# PowerIOShield.net
KiCad netlist of a schematic drawn in EAGLE
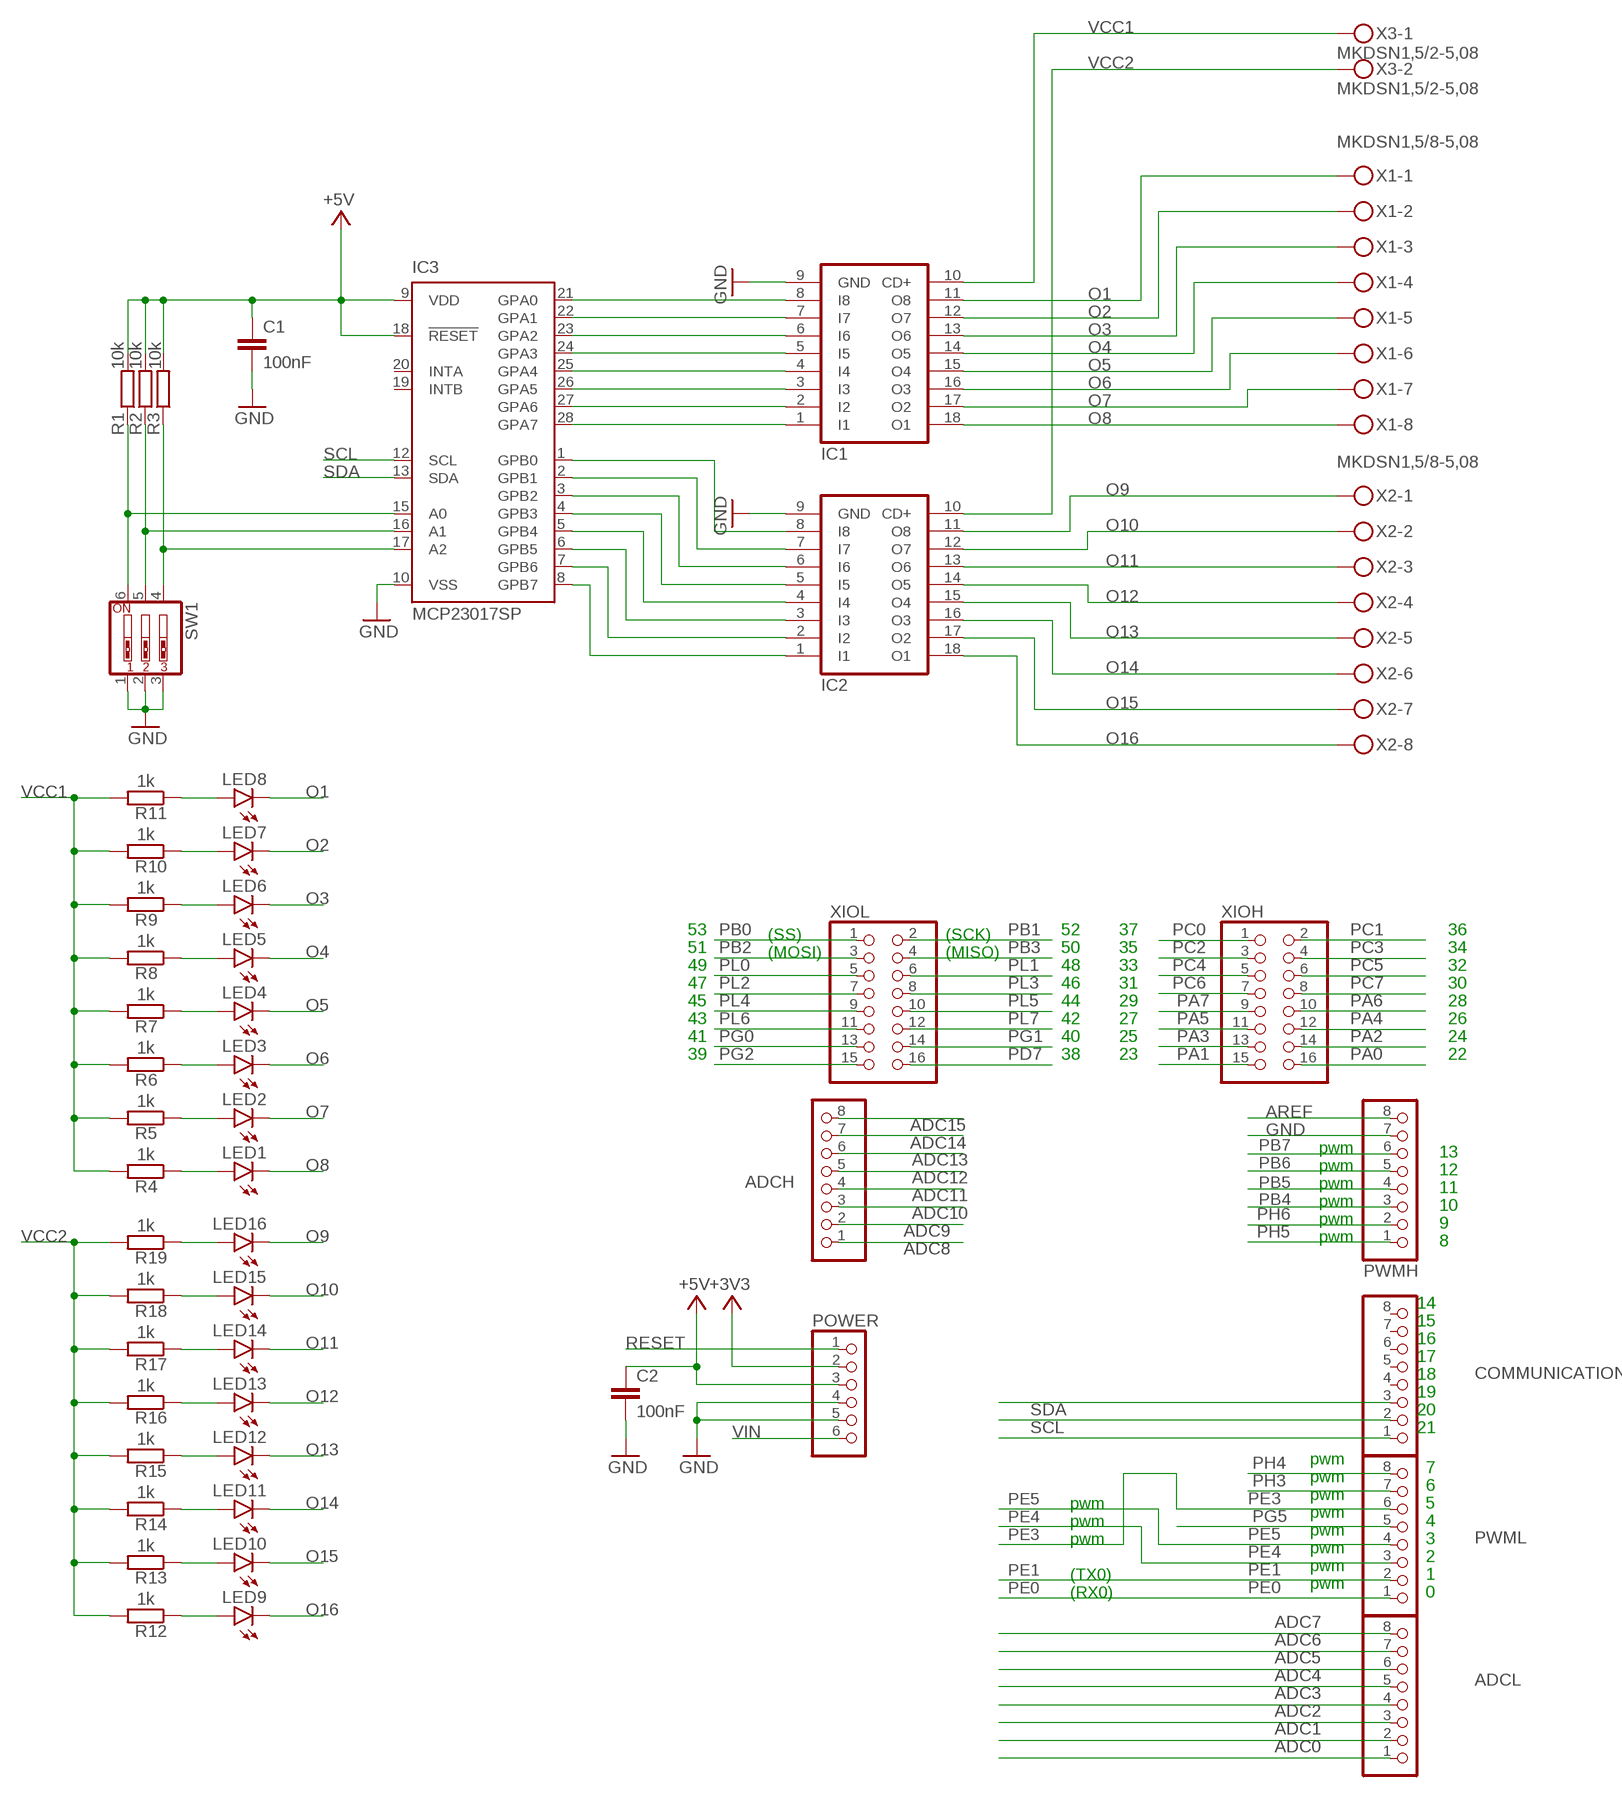
[diagram p0: schematic, sheet 1]

(export (version "E")
  (design (tool "Eeschema 10.0.6"))
  (components
    (comp (ref "ADCH")
      (value "PINHD-1X8")
      (footprint "eagle-import:1X08")
      (libsource (lib "eagle-import") (part "PINHD-1X8"))
    )
    (comp (ref "ADCL")
      (value "PINHD-1X8")
      (footprint "eagle-import:1X08")
      (libsource (lib "eagle-import") (part "PINHD-1X8"))
    )
    (comp (ref "C1")
      (value "100nF")
      (footprint "eagle-import:C025-024X044")
      (libsource (lib "eagle-import") (part "C-EU025-024X044"))
    )
    (comp (ref "C2")
      (value "100nF")
      (footprint "eagle-import:C025-024X044")
      (libsource (lib "eagle-import") (part "C-EU025-024X044"))
    )
    (comp (ref "COMMUNICATION")
      (value "PINHD-1X8")
      (footprint "eagle-import:1X08")
      (libsource (lib "eagle-import") (part "PINHD-1X8"))
    )
    (comp (ref "IC1")
      (value "ULN2803A")
      (footprint "eagle-import:DIL18")
      (libsource (lib "eagle-import") (part "ULN2803A"))
    )
    (comp (ref "IC2")
      (value "ULN2803A")
      (footprint "eagle-import:DIL18")
      (libsource (lib "eagle-import") (part "ULN2803A"))
    )
    (comp (ref "IC3")
      (value "MCP23017SP")
      (footprint "eagle-import:DIL28-3")
      (fields (field (name "MF") "MICROCHIP") (field (name "MPN") "MCP23017-E/SP"))
      (libsource (lib "eagle-import") (part "MCP23017SP"))
    )
    (comp (ref "LED1")
      (value "LED3MM")
      (footprint "eagle-import:LED3MM")
      (libsource (lib "eagle-import") (part "LED3MM"))
    )
    (comp (ref "LED2")
      (value "LED3MM")
      (footprint "eagle-import:LED3MM")
      (libsource (lib "eagle-import") (part "LED3MM"))
    )
    (comp (ref "LED3")
      (value "LED3MM")
      (footprint "eagle-import:LED3MM")
      (libsource (lib "eagle-import") (part "LED3MM"))
    )
    (comp (ref "LED4")
      (value "LED3MM")
      (footprint "eagle-import:LED3MM")
      (libsource (lib "eagle-import") (part "LED3MM"))
    )
    (comp (ref "LED5")
      (value "LED3MM")
      (footprint "eagle-import:LED3MM")
      (libsource (lib "eagle-import") (part "LED3MM"))
    )
    (comp (ref "LED6")
      (value "LED3MM")
      (footprint "eagle-import:LED3MM")
      (libsource (lib "eagle-import") (part "LED3MM"))
    )
    (comp (ref "LED7")
      (value "LED3MM")
      (footprint "eagle-import:LED3MM")
      (libsource (lib "eagle-import") (part "LED3MM"))
    )
    (comp (ref "LED8")
      (value "LED3MM")
      (footprint "eagle-import:LED3MM")
      (libsource (lib "eagle-import") (part "LED3MM"))
    )
    (comp (ref "LED9")
      (value "LED3MM")
      (footprint "eagle-import:LED3MM")
      (libsource (lib "eagle-import") (part "LED3MM"))
    )
    (comp (ref "LED10")
      (value "LED3MM")
      (footprint "eagle-import:LED3MM")
      (libsource (lib "eagle-import") (part "LED3MM"))
    )
    (comp (ref "LED11")
      (value "LED3MM")
      (footprint "eagle-import:LED3MM")
      (libsource (lib "eagle-import") (part "LED3MM"))
    )
    (comp (ref "LED12")
      (value "LED3MM")
      (footprint "eagle-import:LED3MM")
      (libsource (lib "eagle-import") (part "LED3MM"))
    )
    (comp (ref "LED13")
      (value "LED3MM")
      (footprint "eagle-import:LED3MM")
      (libsource (lib "eagle-import") (part "LED3MM"))
    )
    (comp (ref "LED14")
      (value "LED3MM")
      (footprint "eagle-import:LED3MM")
      (libsource (lib "eagle-import") (part "LED3MM"))
    )
    (comp (ref "LED15")
      (value "LED3MM")
      (footprint "eagle-import:LED3MM")
      (libsource (lib "eagle-import") (part "LED3MM"))
    )
    (comp (ref "LED16")
      (value "LED3MM")
      (footprint "eagle-import:LED3MM")
      (libsource (lib "eagle-import") (part "LED3MM"))
    )
    (comp (ref "POWER")
      (value "PINHD-1X6")
      (footprint "eagle-import:1X06")
      (libsource (lib "eagle-import") (part "PINHD-1X6"))
    )
    (comp (ref "PWMH")
      (value "PINHD-1X8")
      (footprint "eagle-import:1X08")
      (libsource (lib "eagle-import") (part "PINHD-1X8"))
    )
    (comp (ref "PWML")
      (value "PINHD-1X8")
      (footprint "eagle-import:1X08")
      (libsource (lib "eagle-import") (part "PINHD-1X8"))
    )
    (comp (ref "R1")
      (value "10k")
      (footprint "eagle-import:0204_7")
      (libsource (lib "eagle-import") (part "R-EU_0204/7"))
    )
    (comp (ref "R2")
      (value "10k")
      (footprint "eagle-import:0204_7")
      (libsource (lib "eagle-import") (part "R-EU_0204/7"))
    )
    (comp (ref "R3")
      (value "10k")
      (footprint "eagle-import:0204_7")
      (libsource (lib "eagle-import") (part "R-EU_0204/7"))
    )
    (comp (ref "R4")
      (value "1k")
      (footprint "eagle-import:0204_7")
      (libsource (lib "eagle-import") (part "R-EU_0204/7"))
    )
    (comp (ref "R5")
      (value "1k")
      (footprint "eagle-import:0204_7")
      (libsource (lib "eagle-import") (part "R-EU_0204/7"))
    )
    (comp (ref "R6")
      (value "1k")
      (footprint "eagle-import:0204_7")
      (libsource (lib "eagle-import") (part "R-EU_0204/7"))
    )
    (comp (ref "R7")
      (value "1k")
      (footprint "eagle-import:0204_7")
      (libsource (lib "eagle-import") (part "R-EU_0204/7"))
    )
    (comp (ref "R8")
      (value "1k")
      (footprint "eagle-import:0204_7")
      (libsource (lib "eagle-import") (part "R-EU_0204/7"))
    )
    (comp (ref "R9")
      (value "1k")
      (footprint "eagle-import:0204_7")
      (libsource (lib "eagle-import") (part "R-EU_0204/7"))
    )
    (comp (ref "R10")
      (value "1k")
      (footprint "eagle-import:0204_7")
      (libsource (lib "eagle-import") (part "R-EU_0204/7"))
    )
    (comp (ref "R11")
      (value "1k")
      (footprint "eagle-import:0204_7")
      (libsource (lib "eagle-import") (part "R-EU_0204/7"))
    )
    (comp (ref "R12")
      (value "1k")
      (footprint "eagle-import:0204_7")
      (libsource (lib "eagle-import") (part "R-EU_0204/7"))
    )
    (comp (ref "R13")
      (value "1k")
      (footprint "eagle-import:0204_7")
      (libsource (lib "eagle-import") (part "R-EU_0204/7"))
    )
    (comp (ref "R14")
      (value "1k")
      (footprint "eagle-import:0204_7")
      (libsource (lib "eagle-import") (part "R-EU_0204/7"))
    )
    (comp (ref "R15")
      (value "1k")
      (footprint "eagle-import:0204_7")
      (libsource (lib "eagle-import") (part "R-EU_0204/7"))
    )
    (comp (ref "R16")
      (value "1k")
      (footprint "eagle-import:0204_7")
      (libsource (lib "eagle-import") (part "R-EU_0204/7"))
    )
    (comp (ref "R17")
      (value "1k")
      (footprint "eagle-import:0204_7")
      (libsource (lib "eagle-import") (part "R-EU_0204/7"))
    )
    (comp (ref "R18")
      (value "1k")
      (footprint "eagle-import:0204_7")
      (libsource (lib "eagle-import") (part "R-EU_0204/7"))
    )
    (comp (ref "R19")
      (value "1k")
      (footprint "eagle-import:0204_7")
      (libsource (lib "eagle-import") (part "R-EU_0204/7"))
    )
    (comp (ref "SW1")
      (value "SW_DIP-3")
      (footprint "eagle-import:EDG-03")
      (libsource (lib "eagle-import") (part "SW_DIP-3"))
    )
    (comp (ref "X1")
      (value "MKDSN1,5/8-5,08")
      (footprint "eagle-import:MKDSN1,5_8-5,08")
      (libsource (lib "eagle-import") (part "MKDSN1,5/8-5,08"))
    )
    (comp (ref "X2")
      (value "MKDSN1,5/8-5,08")
      (footprint "eagle-import:MKDSN1,5_8-5,08")
      (libsource (lib "eagle-import") (part "MKDSN1,5/8-5,08"))
    )
    (comp (ref "X3")
      (value "MKDSN1,5/2-5,08")
      (footprint "eagle-import:MKDSN1,5_2-5,08")
      (libsource (lib "eagle-import") (part "MKDSN1,5/2-5,08"))
    )
    (comp (ref "XIOH")
      (value "PINHD-2X8")
      (footprint "eagle-import:2X08")
      (libsource (lib "eagle-import") (part "PINHD-2X8"))
    )
    (comp (ref "XIOL")
      (value "PINHD-2X8")
      (footprint "eagle-import:2X08")
      (libsource (lib "eagle-import") (part "PINHD-2X8"))
    )
  )
  (nets
    (net (code "1") (name "+3V3") (class "Default")
      (node (ref "POWER") (pin "2") (pinfunction "2_2") (pintype "passive"))
    )
    (net (code "2") (name "+5V") (class "Default")
      (node (ref "C1") (pin "1") (pinfunction "1_1") (pintype "passive"))
      (node (ref "C2") (pin "1") (pinfunction "1_1") (pintype "passive"))
      (node (ref "IC3") (pin "18") (pinfunction "~{RESET}_18") (pintype "input"))
      (node (ref "IC3") (pin "9") (pinfunction "VDD_9") (pintype "power_in"))
      (node (ref "POWER") (pin "3") (pinfunction "3_3") (pintype "passive"))
      (node (ref "R1") (pin "2") (pinfunction "2_2") (pintype "passive"))
      (node (ref "R2") (pin "2") (pinfunction "2_2") (pintype "passive"))
      (node (ref "R3") (pin "2") (pinfunction "2_2") (pintype "passive"))
    )
    (net (code "3") (name "/ADC0") (class "Default")
      (node (ref "ADCL") (pin "1") (pinfunction "1_1") (pintype "passive"))
    )
    (net (code "4") (name "/ADC1") (class "Default")
      (node (ref "ADCL") (pin "2") (pinfunction "2_2") (pintype "passive"))
    )
    (net (code "5") (name "/ADC2") (class "Default")
      (node (ref "ADCL") (pin "3") (pinfunction "3_3") (pintype "passive"))
    )
    (net (code "6") (name "/ADC3") (class "Default")
      (node (ref "ADCL") (pin "4") (pinfunction "4_4") (pintype "passive"))
    )
    (net (code "7") (name "/ADC4") (class "Default")
      (node (ref "ADCL") (pin "5") (pinfunction "5_5") (pintype "passive"))
    )
    (net (code "8") (name "/ADC5") (class "Default")
      (node (ref "ADCL") (pin "6") (pinfunction "6_6") (pintype "passive"))
    )
    (net (code "9") (name "/ADC6") (class "Default")
      (node (ref "ADCL") (pin "7") (pinfunction "7_7") (pintype "passive"))
    )
    (net (code "10") (name "/ADC7") (class "Default")
      (node (ref "ADCL") (pin "8") (pinfunction "8_8") (pintype "passive"))
    )
    (net (code "11") (name "/ADC8") (class "Default")
      (node (ref "ADCH") (pin "1") (pinfunction "1_1") (pintype "passive"))
    )
    (net (code "12") (name "/ADC9") (class "Default")
      (node (ref "ADCH") (pin "2") (pinfunction "2_2") (pintype "passive"))
    )
    (net (code "13") (name "/ADC10") (class "Default")
      (node (ref "ADCH") (pin "3") (pinfunction "3_3") (pintype "passive"))
    )
    (net (code "14") (name "/ADC11") (class "Default")
      (node (ref "ADCH") (pin "4") (pinfunction "4_4") (pintype "passive"))
    )
    (net (code "15") (name "/ADC12") (class "Default")
      (node (ref "ADCH") (pin "5") (pinfunction "5_5") (pintype "passive"))
    )
    (net (code "16") (name "/ADC13") (class "Default")
      (node (ref "ADCH") (pin "6") (pinfunction "6_6") (pintype "passive"))
    )
    (net (code "17") (name "/ADC14") (class "Default")
      (node (ref "ADCH") (pin "7") (pinfunction "7_7") (pintype "passive"))
    )
    (net (code "18") (name "/ADC15") (class "Default")
      (node (ref "ADCH") (pin "8") (pinfunction "8_8") (pintype "passive"))
    )
    (net (code "19") (name "/AREF") (class "Default")
      (node (ref "PWMH") (pin "8") (pinfunction "8_8") (pintype "passive"))
    )
    (net (code "20") (name "/O1") (class "Default")
      (node (ref "IC1") (pin "11") (pinfunction "O8_11") (pintype "open_collector"))
      (node (ref "LED8") (pin "K") (pinfunction "C_K") (pintype "passive"))
      (node (ref "X1") (pin "1") (pinfunction "KL_1") (pintype "passive"))
    )
    (net (code "21") (name "/O2") (class "Default")
      (node (ref "IC1") (pin "12") (pinfunction "O7_12") (pintype "open_collector"))
      (node (ref "LED7") (pin "K") (pinfunction "C_K") (pintype "passive"))
      (node (ref "X1") (pin "2") (pinfunction "KL_2") (pintype "passive"))
    )
    (net (code "22") (name "/O3") (class "Default")
      (node (ref "IC1") (pin "13") (pinfunction "O6_13") (pintype "open_collector"))
      (node (ref "LED6") (pin "K") (pinfunction "C_K") (pintype "passive"))
      (node (ref "X1") (pin "3") (pinfunction "KL_3") (pintype "passive"))
    )
    (net (code "23") (name "/O4") (class "Default")
      (node (ref "IC1") (pin "14") (pinfunction "O5_14") (pintype "open_collector"))
      (node (ref "LED5") (pin "K") (pinfunction "C_K") (pintype "passive"))
      (node (ref "X1") (pin "4") (pinfunction "KL_4") (pintype "passive"))
    )
    (net (code "24") (name "/O5") (class "Default")
      (node (ref "IC1") (pin "15") (pinfunction "O4_15") (pintype "open_collector"))
      (node (ref "LED4") (pin "K") (pinfunction "C_K") (pintype "passive"))
      (node (ref "X1") (pin "5") (pinfunction "KL_5") (pintype "passive"))
    )
    (net (code "25") (name "/O6") (class "Default")
      (node (ref "IC1") (pin "16") (pinfunction "O3_16") (pintype "open_collector"))
      (node (ref "LED3") (pin "K") (pinfunction "C_K") (pintype "passive"))
      (node (ref "X1") (pin "6") (pinfunction "KL_6") (pintype "passive"))
    )
    (net (code "26") (name "/O7") (class "Default")
      (node (ref "IC1") (pin "17") (pinfunction "O2_17") (pintype "open_collector"))
      (node (ref "LED2") (pin "K") (pinfunction "C_K") (pintype "passive"))
      (node (ref "X1") (pin "7") (pinfunction "KL_7") (pintype "passive"))
    )
    (net (code "27") (name "/O8") (class "Default")
      (node (ref "IC1") (pin "18") (pinfunction "O1_18") (pintype "open_collector"))
      (node (ref "LED1") (pin "K") (pinfunction "C_K") (pintype "passive"))
      (node (ref "X1") (pin "8") (pinfunction "KL_8") (pintype "passive"))
    )
    (net (code "28") (name "/O9") (class "Default")
      (node (ref "IC2") (pin "11") (pinfunction "O8_11") (pintype "open_collector"))
      (node (ref "LED16") (pin "K") (pinfunction "C_K") (pintype "passive"))
      (node (ref "X2") (pin "1") (pinfunction "KL_1") (pintype "passive"))
    )
    (net (code "29") (name "/O10") (class "Default")
      (node (ref "IC2") (pin "12") (pinfunction "O7_12") (pintype "open_collector"))
      (node (ref "LED15") (pin "K") (pinfunction "C_K") (pintype "passive"))
      (node (ref "X2") (pin "2") (pinfunction "KL_2") (pintype "passive"))
    )
    (net (code "30") (name "/O11") (class "Default")
      (node (ref "IC2") (pin "13") (pinfunction "O6_13") (pintype "open_collector"))
      (node (ref "LED14") (pin "K") (pinfunction "C_K") (pintype "passive"))
      (node (ref "X2") (pin "3") (pinfunction "KL_3") (pintype "passive"))
    )
    (net (code "31") (name "/O12") (class "Default")
      (node (ref "IC2") (pin "14") (pinfunction "O5_14") (pintype "open_collector"))
      (node (ref "LED13") (pin "K") (pinfunction "C_K") (pintype "passive"))
      (node (ref "X2") (pin "4") (pinfunction "KL_4") (pintype "passive"))
    )
    (net (code "32") (name "/O13") (class "Default")
      (node (ref "IC2") (pin "15") (pinfunction "O4_15") (pintype "open_collector"))
      (node (ref "LED12") (pin "K") (pinfunction "C_K") (pintype "passive"))
      (node (ref "X2") (pin "5") (pinfunction "KL_5") (pintype "passive"))
    )
    (net (code "33") (name "/O14") (class "Default")
      (node (ref "IC2") (pin "16") (pinfunction "O3_16") (pintype "open_collector"))
      (node (ref "LED11") (pin "K") (pinfunction "C_K") (pintype "passive"))
      (node (ref "X2") (pin "6") (pinfunction "KL_6") (pintype "passive"))
    )
    (net (code "34") (name "/O15") (class "Default")
      (node (ref "IC2") (pin "17") (pinfunction "O2_17") (pintype "open_collector"))
      (node (ref "LED10") (pin "K") (pinfunction "C_K") (pintype "passive"))
      (node (ref "X2") (pin "7") (pinfunction "KL_7") (pintype "passive"))
    )
    (net (code "35") (name "/O16") (class "Default")
      (node (ref "IC2") (pin "18") (pinfunction "O1_18") (pintype "open_collector"))
      (node (ref "LED9") (pin "K") (pinfunction "C_K") (pintype "passive"))
      (node (ref "X2") (pin "8") (pinfunction "KL_8") (pintype "passive"))
    )
    (net (code "36") (name "/PA0") (class "Default")
      (node (ref "XIOH") (pin "16") (pinfunction "16_16") (pintype "passive"))
    )
    (net (code "37") (name "/PA1") (class "Default")
      (node (ref "XIOH") (pin "15") (pinfunction "15_15") (pintype "passive"))
    )
    (net (code "38") (name "/PA2") (class "Default")
      (node (ref "XIOH") (pin "14") (pinfunction "14_14") (pintype "passive"))
    )
    (net (code "39") (name "/PA3") (class "Default")
      (node (ref "XIOH") (pin "13") (pinfunction "13_13") (pintype "passive"))
    )
    (net (code "40") (name "/PA4") (class "Default")
      (node (ref "XIOH") (pin "12") (pinfunction "12_12") (pintype "passive"))
    )
    (net (code "41") (name "/PA5") (class "Default")
      (node (ref "XIOH") (pin "11") (pinfunction "11_11") (pintype "passive"))
    )
    (net (code "42") (name "/PA6") (class "Default")
      (node (ref "XIOH") (pin "10") (pinfunction "10_10") (pintype "passive"))
    )
    (net (code "43") (name "/PA7") (class "Default")
      (node (ref "XIOH") (pin "9") (pinfunction "9_9") (pintype "passive"))
    )
    (net (code "44") (name "/PB0") (class "Default")
      (node (ref "XIOL") (pin "1") (pinfunction "1_1") (pintype "passive"))
    )
    (net (code "45") (name "/PB1") (class "Default")
      (node (ref "XIOL") (pin "2") (pinfunction "2_2") (pintype "passive"))
    )
    (net (code "46") (name "/PB2") (class "Default")
      (node (ref "XIOL") (pin "3") (pinfunction "3_3") (pintype "passive"))
    )
    (net (code "47") (name "/PB3") (class "Default")
      (node (ref "XIOL") (pin "4") (pinfunction "4_4") (pintype "passive"))
    )
    (net (code "48") (name "/PB4") (class "Default")
      (node (ref "PWMH") (pin "3") (pinfunction "3_3") (pintype "passive"))
    )
    (net (code "49") (name "/PB5") (class "Default")
      (node (ref "PWMH") (pin "4") (pinfunction "4_4") (pintype "passive"))
    )
    (net (code "50") (name "/PB6") (class "Default")
      (node (ref "PWMH") (pin "5") (pinfunction "5_5") (pintype "passive"))
    )
    (net (code "51") (name "/PB7") (class "Default")
      (node (ref "PWMH") (pin "6") (pinfunction "6_6") (pintype "passive"))
    )
    (net (code "52") (name "/PC0") (class "Default")
      (node (ref "XIOH") (pin "1") (pinfunction "1_1") (pintype "passive"))
    )
    (net (code "53") (name "/PC1") (class "Default")
      (node (ref "XIOH") (pin "2") (pinfunction "2_2") (pintype "passive"))
    )
    (net (code "54") (name "/PC2") (class "Default")
      (node (ref "XIOH") (pin "3") (pinfunction "3_3") (pintype "passive"))
    )
    (net (code "55") (name "/PC3") (class "Default")
      (node (ref "XIOH") (pin "4") (pinfunction "4_4") (pintype "passive"))
    )
    (net (code "56") (name "/PC4") (class "Default")
      (node (ref "XIOH") (pin "5") (pinfunction "5_5") (pintype "passive"))
    )
    (net (code "57") (name "/PC5") (class "Default")
      (node (ref "XIOH") (pin "6") (pinfunction "6_6") (pintype "passive"))
    )
    (net (code "58") (name "/PC6") (class "Default")
      (node (ref "XIOH") (pin "7") (pinfunction "7_7") (pintype "passive"))
    )
    (net (code "59") (name "/PC7") (class "Default")
      (node (ref "XIOH") (pin "8") (pinfunction "8_8") (pintype "passive"))
    )
    (net (code "60") (name "/PD7") (class "Default")
      (node (ref "XIOL") (pin "16") (pinfunction "16_16") (pintype "passive"))
    )
    (net (code "61") (name "/PE0") (class "Default")
      (node (ref "PWML") (pin "1") (pinfunction "1_1") (pintype "passive"))
    )
    (net (code "62") (name "/PE1") (class "Default")
      (node (ref "PWML") (pin "2") (pinfunction "2_2") (pintype "passive"))
    )
    (net (code "63") (name "/PE3") (class "Default")
      (node (ref "PWML") (pin "6") (pinfunction "6_6") (pintype "passive"))
    )
    (net (code "64") (name "/PE4") (class "Default")
      (node (ref "PWML") (pin "3") (pinfunction "3_3") (pintype "passive"))
    )
    (net (code "65") (name "/PE5") (class "Default")
      (node (ref "PWML") (pin "4") (pinfunction "4_4") (pintype "passive"))
    )
    (net (code "66") (name "/PG0") (class "Default")
      (node (ref "XIOL") (pin "13") (pinfunction "13_13") (pintype "passive"))
    )
    (net (code "67") (name "/PG1") (class "Default")
      (node (ref "XIOL") (pin "14") (pinfunction "14_14") (pintype "passive"))
    )
    (net (code "68") (name "/PG2") (class "Default")
      (node (ref "XIOL") (pin "15") (pinfunction "15_15") (pintype "passive"))
    )
    (net (code "69") (name "/PG5") (class "Default")
      (node (ref "PWML") (pin "5") (pinfunction "5_5") (pintype "passive"))
    )
    (net (code "70") (name "/PH3") (class "Default")
      (node (ref "PWML") (pin "7") (pinfunction "7_7") (pintype "passive"))
    )
    (net (code "71") (name "/PH4") (class "Default")
      (node (ref "PWML") (pin "8") (pinfunction "8_8") (pintype "passive"))
    )
    (net (code "72") (name "/PH5") (class "Default")
      (node (ref "PWMH") (pin "1") (pinfunction "1_1") (pintype "passive"))
    )
    (net (code "73") (name "/PH6") (class "Default")
      (node (ref "PWMH") (pin "2") (pinfunction "2_2") (pintype "passive"))
    )
    (net (code "74") (name "/PL0") (class "Default")
      (node (ref "XIOL") (pin "5") (pinfunction "5_5") (pintype "passive"))
    )
    (net (code "75") (name "/PL1") (class "Default")
      (node (ref "XIOL") (pin "6") (pinfunction "6_6") (pintype "passive"))
    )
    (net (code "76") (name "/PL2") (class "Default")
      (node (ref "XIOL") (pin "7") (pinfunction "7_7") (pintype "passive"))
    )
    (net (code "77") (name "/PL3") (class "Default")
      (node (ref "XIOL") (pin "8") (pinfunction "8_8") (pintype "passive"))
    )
    (net (code "78") (name "/PL4") (class "Default")
      (node (ref "XIOL") (pin "9") (pinfunction "9_9") (pintype "passive"))
    )
    (net (code "79") (name "/PL5") (class "Default")
      (node (ref "XIOL") (pin "10") (pinfunction "10_10") (pintype "passive"))
    )
    (net (code "80") (name "/PL6") (class "Default")
      (node (ref "XIOL") (pin "11") (pinfunction "11_11") (pintype "passive"))
    )
    (net (code "81") (name "/PL7") (class "Default")
      (node (ref "XIOL") (pin "12") (pinfunction "12_12") (pintype "passive"))
    )
    (net (code "82") (name "/RESET") (class "Default")
      (node (ref "POWER") (pin "1") (pinfunction "1_1") (pintype "passive"))
    )
    (net (code "83") (name "/SCL") (class "Default")
      (node (ref "COMMUNICATION") (pin "1") (pinfunction "1_1") (pintype "passive"))
      (node (ref "IC3") (pin "12") (pinfunction "SCL_12") (pintype "input"))
    )
    (net (code "84") (name "/SDA") (class "Default")
      (node (ref "COMMUNICATION") (pin "2") (pinfunction "2_2") (pintype "passive"))
      (node (ref "IC3") (pin "13") (pinfunction "SDA_13") (pintype "bidirectional"))
    )
    (net (code "85") (name "/VCC1") (class "Default")
      (node (ref "IC1") (pin "10") (pinfunction "CD+_10") (pintype "passive"))
      (node (ref "R10") (pin "2") (pinfunction "2_2") (pintype "passive"))
      (node (ref "R11") (pin "2") (pinfunction "2_2") (pintype "passive"))
      (node (ref "R4") (pin "2") (pinfunction "2_2") (pintype "passive"))
      (node (ref "R5") (pin "2") (pinfunction "2_2") (pintype "passive"))
      (node (ref "R6") (pin "2") (pinfunction "2_2") (pintype "passive"))
      (node (ref "R7") (pin "2") (pinfunction "2_2") (pintype "passive"))
      (node (ref "R8") (pin "2") (pinfunction "2_2") (pintype "passive"))
      (node (ref "R9") (pin "2") (pinfunction "2_2") (pintype "passive"))
      (node (ref "X3") (pin "1") (pinfunction "KL_1") (pintype "passive"))
    )
    (net (code "86") (name "/VCC2") (class "Default")
      (node (ref "IC2") (pin "10") (pinfunction "CD+_10") (pintype "passive"))
      (node (ref "R12") (pin "2") (pinfunction "2_2") (pintype "passive"))
      (node (ref "R13") (pin "2") (pinfunction "2_2") (pintype "passive"))
      (node (ref "R14") (pin "2") (pinfunction "2_2") (pintype "passive"))
      (node (ref "R15") (pin "2") (pinfunction "2_2") (pintype "passive"))
      (node (ref "R16") (pin "2") (pinfunction "2_2") (pintype "passive"))
      (node (ref "R17") (pin "2") (pinfunction "2_2") (pintype "passive"))
      (node (ref "R18") (pin "2") (pinfunction "2_2") (pintype "passive"))
      (node (ref "R19") (pin "2") (pinfunction "2_2") (pintype "passive"))
      (node (ref "X3") (pin "2") (pinfunction "KL_2") (pintype "passive"))
    )
    (net (code "87") (name "/VIN") (class "Default")
      (node (ref "POWER") (pin "6") (pinfunction "6_6") (pintype "passive"))
    )
    (net (code "88") (name "GND") (class "Default")
      (node (ref "C1") (pin "2") (pinfunction "2_2") (pintype "passive"))
      (node (ref "C2") (pin "2") (pinfunction "2_2") (pintype "passive"))
      (node (ref "IC1") (pin "9") (pinfunction "GND_9") (pintype "power_in"))
      (node (ref "IC2") (pin "9") (pinfunction "GND_9") (pintype "power_in"))
      (node (ref "IC3") (pin "10") (pinfunction "VSS_10") (pintype "power_in"))
      (node (ref "POWER") (pin "4") (pinfunction "4_4") (pintype "passive"))
      (node (ref "POWER") (pin "5") (pinfunction "5_5") (pintype "passive"))
      (node (ref "PWMH") (pin "7") (pinfunction "7_7") (pintype "passive"))
      (node (ref "SW1") (pin "1") (pinfunction "1_1") (pintype "passive"))
      (node (ref "SW1") (pin "2") (pinfunction "2_2") (pintype "passive"))
      (node (ref "SW1") (pin "3") (pinfunction "3_3") (pintype "passive"))
    )
    (net (code "89") (name "Net-(IC1-I1)") (class "Default")
      (node (ref "IC1") (pin "1") (pinfunction "I1_1") (pintype "input"))
      (node (ref "IC3") (pin "28") (pinfunction "GPA7_28") (pintype "bidirectional"))
    )
    (net (code "90") (name "Net-(IC1-I2)") (class "Default")
      (node (ref "IC1") (pin "2") (pinfunction "I2_2") (pintype "input"))
      (node (ref "IC3") (pin "27") (pinfunction "GPA6_27") (pintype "bidirectional"))
    )
    (net (code "91") (name "Net-(IC1-I3)") (class "Default")
      (node (ref "IC1") (pin "3") (pinfunction "I3_3") (pintype "input"))
      (node (ref "IC3") (pin "26") (pinfunction "GPA5_26") (pintype "bidirectional"))
    )
    (net (code "92") (name "Net-(IC1-I4)") (class "Default")
      (node (ref "IC1") (pin "4") (pinfunction "I4_4") (pintype "input"))
      (node (ref "IC3") (pin "25") (pinfunction "GPA4_25") (pintype "bidirectional"))
    )
    (net (code "93") (name "Net-(IC1-I5)") (class "Default")
      (node (ref "IC1") (pin "5") (pinfunction "I5_5") (pintype "input"))
      (node (ref "IC3") (pin "24") (pinfunction "GPA3_24") (pintype "bidirectional"))
    )
    (net (code "94") (name "Net-(IC1-I6)") (class "Default")
      (node (ref "IC1") (pin "6") (pinfunction "I6_6") (pintype "input"))
      (node (ref "IC3") (pin "23") (pinfunction "GPA2_23") (pintype "bidirectional"))
    )
    (net (code "95") (name "Net-(IC1-I7)") (class "Default")
      (node (ref "IC1") (pin "7") (pinfunction "I7_7") (pintype "input"))
      (node (ref "IC3") (pin "22") (pinfunction "GPA1_22") (pintype "bidirectional"))
    )
    (net (code "96") (name "Net-(IC1-I8)") (class "Default")
      (node (ref "IC1") (pin "8") (pinfunction "I8_8") (pintype "input"))
      (node (ref "IC3") (pin "21") (pinfunction "GPA0_21") (pintype "bidirectional"))
    )
    (net (code "97") (name "Net-(IC2-I1)") (class "Default")
      (node (ref "IC2") (pin "1") (pinfunction "I1_1") (pintype "input"))
      (node (ref "IC3") (pin "8") (pinfunction "GPB7_8") (pintype "bidirectional"))
    )
    (net (code "98") (name "Net-(IC2-I2)") (class "Default")
      (node (ref "IC2") (pin "2") (pinfunction "I2_2") (pintype "input"))
      (node (ref "IC3") (pin "7") (pinfunction "GPB6_7") (pintype "bidirectional"))
    )
    (net (code "99") (name "Net-(IC2-I3)") (class "Default")
      (node (ref "IC2") (pin "3") (pinfunction "I3_3") (pintype "input"))
      (node (ref "IC3") (pin "6") (pinfunction "GPB5_6") (pintype "bidirectional"))
    )
    (net (code "100") (name "Net-(IC2-I4)") (class "Default")
      (node (ref "IC2") (pin "4") (pinfunction "I4_4") (pintype "input"))
      (node (ref "IC3") (pin "5") (pinfunction "GPB4_5") (pintype "bidirectional"))
    )
    (net (code "101") (name "Net-(IC2-I5)") (class "Default")
      (node (ref "IC2") (pin "5") (pinfunction "I5_5") (pintype "input"))
      (node (ref "IC3") (pin "4") (pinfunction "GPB3_4") (pintype "bidirectional"))
    )
    (net (code "102") (name "Net-(IC2-I6)") (class "Default")
      (node (ref "IC2") (pin "6") (pinfunction "I6_6") (pintype "input"))
      (node (ref "IC3") (pin "3") (pinfunction "GPB2_3") (pintype "bidirectional"))
    )
    (net (code "103") (name "Net-(IC2-I7)") (class "Default")
      (node (ref "IC2") (pin "7") (pinfunction "I7_7") (pintype "input"))
      (node (ref "IC3") (pin "2") (pinfunction "GPB1_2") (pintype "bidirectional"))
    )
    (net (code "104") (name "Net-(IC2-I8)") (class "Default")
      (node (ref "IC2") (pin "8") (pinfunction "I8_8") (pintype "input"))
      (node (ref "IC3") (pin "1") (pinfunction "GPB0_1") (pintype "bidirectional"))
    )
    (net (code "105") (name "Net-(IC3-A0)") (class "Default")
      (node (ref "IC3") (pin "15") (pinfunction "A0_15") (pintype "input"))
      (node (ref "R1") (pin "1") (pinfunction "1_1") (pintype "passive"))
      (node (ref "SW1") (pin "6") (pinfunction "6_6") (pintype "passive"))
    )
    (net (code "106") (name "Net-(IC3-A1)") (class "Default")
      (node (ref "IC3") (pin "16") (pinfunction "A1_16") (pintype "input"))
      (node (ref "R2") (pin "1") (pinfunction "1_1") (pintype "passive"))
      (node (ref "SW1") (pin "5") (pinfunction "5_5") (pintype "passive"))
    )
    (net (code "107") (name "Net-(IC3-A2)") (class "Default")
      (node (ref "IC3") (pin "17") (pinfunction "A2_17") (pintype "input"))
      (node (ref "R3") (pin "1") (pinfunction "1_1") (pintype "passive"))
      (node (ref "SW1") (pin "4") (pinfunction "4_4") (pintype "passive"))
    )
    (net (code "108") (name "Net-(LED1-PadA)") (class "Default")
      (node (ref "LED1") (pin "A") (pinfunction "A_A") (pintype "passive"))
      (node (ref "R4") (pin "1") (pinfunction "1_1") (pintype "passive"))
    )
    (net (code "109") (name "Net-(LED2-PadA)") (class "Default")
      (node (ref "LED2") (pin "A") (pinfunction "A_A") (pintype "passive"))
      (node (ref "R5") (pin "1") (pinfunction "1_1") (pintype "passive"))
    )
    (net (code "110") (name "Net-(LED3-PadA)") (class "Default")
      (node (ref "LED3") (pin "A") (pinfunction "A_A") (pintype "passive"))
      (node (ref "R6") (pin "1") (pinfunction "1_1") (pintype "passive"))
    )
    (net (code "111") (name "Net-(LED4-PadA)") (class "Default")
      (node (ref "LED4") (pin "A") (pinfunction "A_A") (pintype "passive"))
      (node (ref "R7") (pin "1") (pinfunction "1_1") (pintype "passive"))
    )
    (net (code "112") (name "Net-(LED5-PadA)") (class "Default")
      (node (ref "LED5") (pin "A") (pinfunction "A_A") (pintype "passive"))
      (node (ref "R8") (pin "1") (pinfunction "1_1") (pintype "passive"))
    )
    (net (code "113") (name "Net-(LED6-PadA)") (class "Default")
      (node (ref "LED6") (pin "A") (pinfunction "A_A") (pintype "passive"))
      (node (ref "R9") (pin "1") (pinfunction "1_1") (pintype "passive"))
    )
    (net (code "114") (name "Net-(LED7-PadA)") (class "Default")
      (node (ref "LED7") (pin "A") (pinfunction "A_A") (pintype "passive"))
      (node (ref "R10") (pin "1") (pinfunction "1_1") (pintype "passive"))
    )
    (net (code "115") (name "Net-(LED8-PadA)") (class "Default")
      (node (ref "LED8") (pin "A") (pinfunction "A_A") (pintype "passive"))
      (node (ref "R11") (pin "1") (pinfunction "1_1") (pintype "passive"))
    )
    (net (code "116") (name "Net-(LED9-PadA)") (class "Default")
      (node (ref "LED9") (pin "A") (pinfunction "A_A") (pintype "passive"))
      (node (ref "R12") (pin "1") (pinfunction "1_1") (pintype "passive"))
    )
    (net (code "117") (name "Net-(LED10-PadA)") (class "Default")
      (node (ref "LED10") (pin "A") (pinfunction "A_A") (pintype "passive"))
      (node (ref "R13") (pin "1") (pinfunction "1_1") (pintype "passive"))
    )
    (net (code "118") (name "Net-(LED11-PadA)") (class "Default")
      (node (ref "LED11") (pin "A") (pinfunction "A_A") (pintype "passive"))
      (node (ref "R14") (pin "1") (pinfunction "1_1") (pintype "passive"))
    )
    (net (code "119") (name "Net-(LED12-PadA)") (class "Default")
      (node (ref "LED12") (pin "A") (pinfunction "A_A") (pintype "passive"))
      (node (ref "R15") (pin "1") (pinfunction "1_1") (pintype "passive"))
    )
    (net (code "120") (name "Net-(LED13-PadA)") (class "Default")
      (node (ref "LED13") (pin "A") (pinfunction "A_A") (pintype "passive"))
      (node (ref "R16") (pin "1") (pinfunction "1_1") (pintype "passive"))
    )
    (net (code "121") (name "Net-(LED14-PadA)") (class "Default")
      (node (ref "LED14") (pin "A") (pinfunction "A_A") (pintype "passive"))
      (node (ref "R17") (pin "1") (pinfunction "1_1") (pintype "passive"))
    )
    (net (code "122") (name "Net-(LED15-PadA)") (class "Default")
      (node (ref "LED15") (pin "A") (pinfunction "A_A") (pintype "passive"))
      (node (ref "R18") (pin "1") (pinfunction "1_1") (pintype "passive"))
    )
    (net (code "123") (name "Net-(LED16-PadA)") (class "Default")
      (node (ref "LED16") (pin "A") (pinfunction "A_A") (pintype "passive"))
      (node (ref "R19") (pin "1") (pinfunction "1_1") (pintype "passive"))
    )
    (net (code "124") (name "unconnected-(COMMUNICATION-Pad3)") (class "Default")
      (node (ref "COMMUNICATION") (pin "3") (pinfunction "3_3") (pintype "passive"))
    )
    (net (code "125") (name "unconnected-(COMMUNICATION-Pad4)") (class "Default")
      (node (ref "COMMUNICATION") (pin "4") (pinfunction "4_4") (pintype "passive"))
    )
    (net (code "126") (name "unconnected-(COMMUNICATION-Pad5)") (class "Default")
      (node (ref "COMMUNICATION") (pin "5") (pinfunction "5_5") (pintype "passive"))
    )
    (net (code "127") (name "unconnected-(COMMUNICATION-Pad6)") (class "Default")
      (node (ref "COMMUNICATION") (pin "6") (pinfunction "6_6") (pintype "passive"))
    )
    (net (code "128") (name "unconnected-(COMMUNICATION-Pad7)") (class "Default")
      (node (ref "COMMUNICATION") (pin "7") (pinfunction "7_7") (pintype "passive"))
    )
    (net (code "129") (name "unconnected-(COMMUNICATION-Pad8)") (class "Default")
      (node (ref "COMMUNICATION") (pin "8") (pinfunction "8_8") (pintype "passive"))
    )
    (net (code "130") (name "unconnected-(IC3-INTA-Pad20)") (class "Default")
      (node (ref "IC3") (pin "20") (pinfunction "INTA_20") (pintype "output"))
    )
    (net (code "131") (name "unconnected-(IC3-INTB-Pad19)") (class "Default")
      (node (ref "IC3") (pin "19") (pinfunction "INTB_19") (pintype "output"))
    )
  )
)
